# Drone-Schematic-v1.net
KiCad netlist of a schematic drawn in Altium Designer
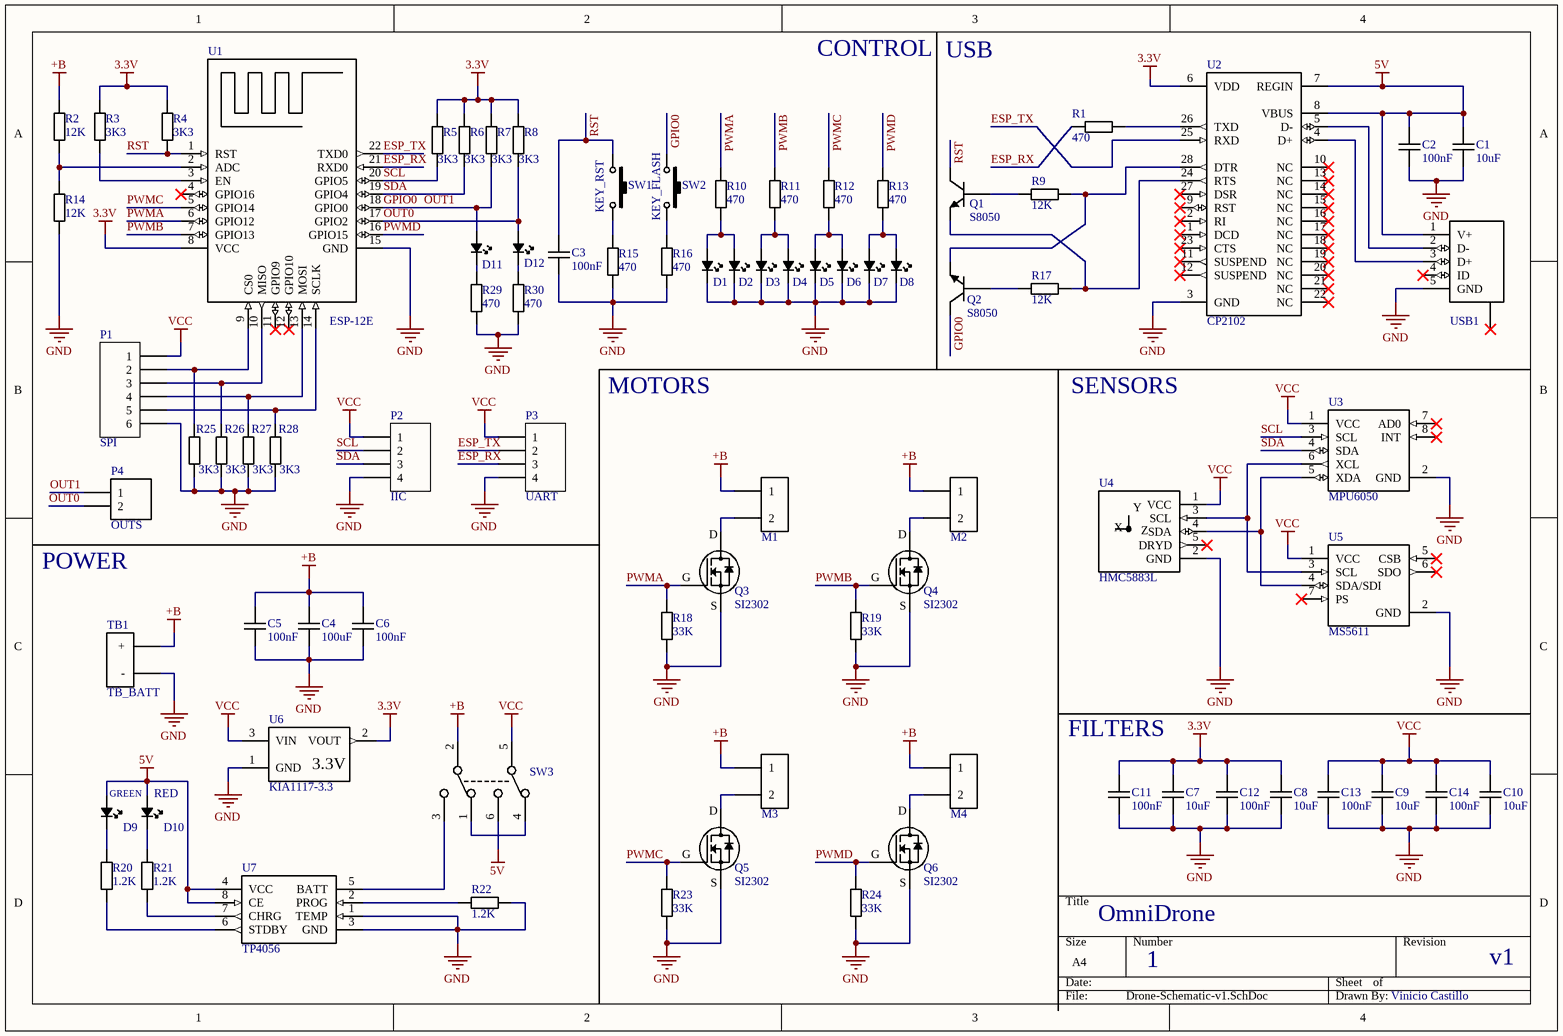
[diagram p0: Drone-Schematic-v1.SchDoc]

(export (version "E")
  (design (tool "Eeschema 10.0.6"))
  (components
    (comp (ref "C1") (value "10uF") (footprint "1206CAP") (libsource (lib "OmniLibrary") (part "Capacitor")))
    (comp (ref "C2") (value "100nF") (footprint "1206CAP") (libsource (lib "OmniLibrary") (part "Capacitor")))
    (comp (ref "C3") (value "100nF") (footprint "1206CAP") (libsource (lib "OmniLibrary") (part "Capacitor")))
    (comp (ref "C4") (value "100uF") (footprint "1206CAP") (libsource (lib "OmniLibrary") (part "Capacitor")))
    (comp (ref "C5") (value "100nF") (footprint "1206CAP") (libsource (lib "OmniLibrary") (part "Capacitor")))
    (comp (ref "C6") (value "100nF") (footprint "1206CAP") (libsource (lib "OmniLibrary") (part "Capacitor")))
    (comp (ref "C7") (value "10uF") (footprint "1206CAP") (libsource (lib "OmniLibrary") (part "Capacitor")))
    (comp (ref "C8") (value "10uF") (footprint "1206CAP") (libsource (lib "OmniLibrary") (part "Capacitor")))
    (comp (ref "C9") (value "10uF") (footprint "1206CAP") (libsource (lib "OmniLibrary") (part "Capacitor")))
    (comp (ref "C10") (value "10uF") (footprint "1206CAP") (libsource (lib "OmniLibrary") (part "Capacitor")))
    (comp (ref "C11")
      (value "100nF")
      (footprint "1206CAP")
      (libsource (lib "OmniLibrary") (part "Capacitor"))
    )
    (comp (ref "C12")
      (value "100nF")
      (footprint "1206CAP")
      (libsource (lib "OmniLibrary") (part "Capacitor"))
    )
    (comp (ref "C13")
      (value "100nF")
      (footprint "1206CAP")
      (libsource (lib "OmniLibrary") (part "Capacitor"))
    )
    (comp (ref "C14")
      (value "100nF")
      (footprint "1206CAP")
      (libsource (lib "OmniLibrary") (part "Capacitor"))
    )
    (comp (ref "D1")
      (value "LED")
      (footprint "1206DIODE")
      (description "Ligth Emitting Diode (LED)")
      (libsource (lib "OmniLibrary") (part "LED"))
    )
    (comp (ref "D2")
      (value "LED")
      (footprint "1206DIODE")
      (description "Ligth Emitting Diode (LED)")
      (libsource (lib "OmniLibrary") (part "LED"))
    )
    (comp (ref "D3")
      (value "LED")
      (footprint "1206DIODE")
      (description "Ligth Emitting Diode (LED)")
      (libsource (lib "OmniLibrary") (part "LED"))
    )
    (comp (ref "D4")
      (value "LED")
      (footprint "1206DIODE")
      (description "Ligth Emitting Diode (LED)")
      (libsource (lib "OmniLibrary") (part "LED"))
    )
    (comp (ref "D5")
      (value "LED")
      (footprint "1206DIODE")
      (description "Ligth Emitting Diode (LED)")
      (libsource (lib "OmniLibrary") (part "LED"))
    )
    (comp (ref "D6")
      (value "LED")
      (footprint "1206DIODE")
      (description "Ligth Emitting Diode (LED)")
      (libsource (lib "OmniLibrary") (part "LED"))
    )
    (comp (ref "D7")
      (value "LED")
      (footprint "1206DIODE")
      (description "Ligth Emitting Diode (LED)")
      (libsource (lib "OmniLibrary") (part "LED"))
    )
    (comp (ref "D8")
      (value "LED")
      (footprint "1206DIODE")
      (description "Ligth Emitting Diode (LED)")
      (libsource (lib "OmniLibrary") (part "LED"))
    )
    (comp (ref "D9")
      (value "LED")
      (footprint "1206DIODE")
      (description "Ligth Emitting Diode (LED)")
      (libsource (lib "OmniLibrary") (part "LED"))
    )
    (comp (ref "D10")
      (value "LED")
      (footprint "1206DIODE")
      (description "Ligth Emitting Diode (LED)")
      (libsource (lib "OmniLibrary") (part "LED"))
    )
    (comp (ref "D11")
      (value "LED")
      (footprint "1206DIODE")
      (description "Ligth Emitting Diode (LED)")
      (libsource (lib "OmniLibrary") (part "LED"))
    )
    (comp (ref "D12")
      (value "LED")
      (footprint "1206DIODE")
      (description "Ligth Emitting Diode (LED)")
      (libsource (lib "OmniLibrary") (part "LED"))
    )
    (comp (ref "M1")
      (value "TBX2X1")
      (footprint "JST 1.25mm")
      (description "Terminal Block 2 pins, 1 row")
      (libsource (lib "OmniLibrary") (part "TBX2X1"))
    )
    (comp (ref "M2")
      (value "TBX2X1")
      (footprint "JST 1.25mm")
      (description "Terminal Block 2 pins, 1 row")
      (libsource (lib "OmniLibrary") (part "TBX2X1"))
    )
    (comp (ref "M3")
      (value "TBX2X1")
      (footprint "JST 1.25mm")
      (description "Terminal Block 2 pins, 1 row")
      (libsource (lib "OmniLibrary") (part "TBX2X1"))
    )
    (comp (ref "M4")
      (value "TBX2X1")
      (footprint "JST 1.25mm")
      (description "Terminal Block 2 pins, 1 row")
      (libsource (lib "OmniLibrary") (part "TBX2X1"))
    )
    (comp (ref "P1")
      (value "SPI")
      (footprint "HDR1X6")
      (description "Header, 6-Pin")
      (fields (field (name "PUBLISHER") "Altium Limited"))
      (libsource (lib "OmniLibrary") (part "Header 6"))
    )
    (comp (ref "P2")
      (value "IIC")
      (footprint "HDR1X4")
      (description "Header, 4-Pin")
      (fields (field (name "PUBLISHER") "Altium Limited"))
      (libsource (lib "OmniLibrary") (part "Header 4"))
    )
    (comp (ref "P3")
      (value "UART")
      (footprint "HDR1X4")
      (description "Header, 4-Pin")
      (fields (field (name "PUBLISHER") "Altium Limited"))
      (libsource (lib "OmniLibrary") (part "Header 4"))
    )
    (comp (ref "P4")
      (value "OUTS")
      (footprint "HDR1X2")
      (description "Header, 2-Pin")
      (fields (field (name "PUBLISHER") "Altium Limited"))
      (libsource (lib "OmniLibrary") (part "Header 2"))
    )
    (comp (ref "Q1")
      (value "S8050")
      (footprint "SOT-23(SOT-23-3)")
      (description "Transistor NPN 500mA 25V SOT-23(SOT-23-3) RoHS")
      (libsource (lib "OmniLibrary") (part "S8050"))
    )
    (comp (ref "Q2")
      (value "S8050")
      (footprint "SOT-23(SOT-23-3)")
      (description "Transistor NPN 500mA 25V SOT-23(SOT-23-3) RoHS")
      (libsource (lib "OmniLibrary") (part "S8050"))
    )
    (comp (ref "Q3")
      (value "SI2302")
      (footprint "SOT-23(SOT-23-3)")
      (description "MOSFET N Trench 20V 2.1A 1.2V @ 50uA 72 mO @ 3.6A,4.5V SOT-23(SOT-23-3) RoHS")
      (libsource (lib "OmniLibrary") (part "SI2302"))
    )
    (comp (ref "Q4")
      (value "SI2302")
      (footprint "SOT-23(SOT-23-3)")
      (description "MOSFET N Trench 20V 2.1A 1.2V @ 50uA 72 mO @ 3.6A,4.5V SOT-23(SOT-23-3) RoHS")
      (libsource (lib "OmniLibrary") (part "SI2302"))
    )
    (comp (ref "Q5")
      (value "SI2302")
      (footprint "SOT-23(SOT-23-3)")
      (description "MOSFET N Trench 20V 2.1A 1.2V @ 50uA 72 mO @ 3.6A,4.5V SOT-23(SOT-23-3) RoHS")
      (libsource (lib "OmniLibrary") (part "SI2302"))
    )
    (comp (ref "Q6")
      (value "SI2302")
      (footprint "SOT-23(SOT-23-3)")
      (description "MOSFET N Trench 20V 2.1A 1.2V @ 50uA 72 mO @ 3.6A,4.5V SOT-23(SOT-23-3) RoHS")
      (libsource (lib "OmniLibrary") (part "SI2302"))
    )
    (comp (ref "R1")
      (value "470")
      (footprint "1206RES")
      (description "Passive component")
      (libsource (lib "") (part "Resistor_2"))
    )
    (comp (ref "R2")
      (value "12K")
      (footprint "1206RES")
      (description "Passive component")
      (libsource (lib "OmniLibrary") (part "Resistor"))
    )
    (comp (ref "R3")
      (value "3K3")
      (footprint "1206RES")
      (description "Passive component")
      (libsource (lib "") (part "Resistor_1"))
    )
    (comp (ref "R4")
      (value "3K3")
      (footprint "1206RES")
      (description "Passive component")
      (libsource (lib "") (part "Resistor_1"))
    )
    (comp (ref "R5")
      (value "3K3")
      (footprint "1206RES")
      (description "Passive component")
      (libsource (lib "") (part "Resistor_1"))
    )
    (comp (ref "R6")
      (value "3K3")
      (footprint "1206RES")
      (description "Passive component")
      (libsource (lib "") (part "Resistor_1"))
    )
    (comp (ref "R7")
      (value "3K3")
      (footprint "1206RES")
      (description "Passive component")
      (libsource (lib "") (part "Resistor_1"))
    )
    (comp (ref "R8")
      (value "3K3")
      (footprint "1206RES")
      (description "Passive component")
      (libsource (lib "") (part "Resistor_1"))
    )
    (comp (ref "R9")
      (value "12K")
      (footprint "1206RES")
      (description "Passive component")
      (libsource (lib "") (part "Resistor_2"))
    )
    (comp (ref "R10")
      (value "470")
      (footprint "1206RES")
      (description "Passive component")
      (libsource (lib "") (part "Resistor_1"))
    )
    (comp (ref "R11")
      (value "470")
      (footprint "1206RES")
      (description "Passive component")
      (libsource (lib "") (part "Resistor_1"))
    )
    (comp (ref "R12")
      (value "470")
      (footprint "1206RES")
      (description "Passive component")
      (libsource (lib "") (part "Resistor_1"))
    )
    (comp (ref "R13")
      (value "470")
      (footprint "1206RES")
      (description "Passive component")
      (libsource (lib "") (part "Resistor_1"))
    )
    (comp (ref "R14")
      (value "12K")
      (footprint "1206RES")
      (description "Passive component")
      (libsource (lib "OmniLibrary") (part "Resistor"))
    )
    (comp (ref "R15")
      (value "470")
      (footprint "1206RES")
      (description "Passive component")
      (libsource (lib "") (part "Resistor_1"))
    )
    (comp (ref "R16")
      (value "470")
      (footprint "1206RES")
      (description "Passive component")
      (libsource (lib "") (part "Resistor_1"))
    )
    (comp (ref "R17")
      (value "12K")
      (footprint "1206RES")
      (description "Passive component")
      (libsource (lib "") (part "Resistor_2"))
    )
    (comp (ref "R18")
      (value "33K")
      (footprint "1206RES")
      (description "Passive component")
      (libsource (lib "OmniLibrary") (part "Resistor"))
    )
    (comp (ref "R19")
      (value "33K")
      (footprint "1206RES")
      (description "Passive component")
      (libsource (lib "OmniLibrary") (part "Resistor"))
    )
    (comp (ref "R20")
      (value "1.2K")
      (footprint "1206RES")
      (description "Passive component")
      (libsource (lib "OmniLibrary") (part "Resistor"))
    )
    (comp (ref "R21")
      (value "1.2K")
      (footprint "1206RES")
      (description "Passive component")
      (libsource (lib "OmniLibrary") (part "Resistor"))
    )
    (comp (ref "R22")
      (value "1.2K")
      (footprint "1206RES")
      (description "Passive component")
      (libsource (lib "") (part "Resistor_2"))
    )
    (comp (ref "R23")
      (value "33K")
      (footprint "1206RES")
      (description "Passive component")
      (libsource (lib "OmniLibrary") (part "Resistor"))
    )
    (comp (ref "R24")
      (value "33K")
      (footprint "1206RES")
      (description "Passive component")
      (libsource (lib "OmniLibrary") (part "Resistor"))
    )
    (comp (ref "R25")
      (value "3K3")
      (footprint "1206RES")
      (description "Passive component")
      (libsource (lib "") (part "Resistor_1"))
    )
    (comp (ref "R26")
      (value "3K3")
      (footprint "1206RES")
      (description "Passive component")
      (libsource (lib "") (part "Resistor_1"))
    )
    (comp (ref "R27")
      (value "3K3")
      (footprint "1206RES")
      (description "Passive component")
      (libsource (lib "") (part "Resistor_1"))
    )
    (comp (ref "R28")
      (value "3K3")
      (footprint "1206RES")
      (description "Passive component")
      (libsource (lib "") (part "Resistor_1"))
    )
    (comp (ref "R29")
      (value "470")
      (footprint "1206RES")
      (description "Passive component")
      (libsource (lib "OmniLibrary") (part "Resistor"))
    )
    (comp (ref "R30")
      (value "470")
      (footprint "1206RES")
      (description "Passive component")
      (libsource (lib "OmniLibrary") (part "Resistor"))
    )
    (comp (ref "SW1")
      (value "PUSH BUTTON")
      (footprint "Push Button")
      (description "Normally Open (NO) button")
      (libsource (lib "OmniLibrary") (part "PUSH BUTTON"))
    )
    (comp (ref "SW2")
      (value "PUSH BUTTON")
      (footprint "Push Button")
      (description "Normally Open (NO) button")
      (libsource (lib "OmniLibrary") (part "PUSH BUTTON"))
    )
    (comp (ref "SW3")
      (value "SW DPDT")
      (footprint "DPDT SW")
      (description "DPDT Switch")
      (libsource (lib "OmniLibrary") (part "SW DPDT"))
    )
    (comp (ref "TB1")
      (value "TB_BATT")
      (footprint "2P PH2.0mm Pitch")
      (description "Battery terminal block")
      (libsource (lib "OmniLibrary") (part "TB_BATT"))
    )
    (comp (ref "U1")
      (value "ESP-12E")
      (footprint "ESP-12E")
      (description "ESP8266 MCU based WIFI PCB Module")
      (libsource (lib "OmniLibrary") (part "ESP-12E"))
    )
    (comp (ref "U2")
      (value "CP2102")
      (footprint "CP2102")
      (description "USB to UART interface IC 3.3v")
      (libsource (lib "OmniLibrary") (part "CP2102"))
    )
    (comp (ref "U3")
      (value "MPU6050")
      (footprint "MPU6050 - PCB MODULE")
      (description "PCB Module, 3 Axis Analog Gyro Sensors+ 3 Axis Accelerometer, IIC")
      (libsource (lib "OmniLibrary") (part "MPU6050"))
    )
    (comp (ref "U4")
      (value "HMC5883L")
      (footprint "HMC5883L - PCB MODULE")
      (description "PCB Module, Triple Axis Compass Magnetometer Sensor Module, IIC Conn")
      (libsource (lib "OmniLibrary") (part "HMC5883L"))
    )
    (comp (ref "U5")
      (value "MS5611")
      (footprint "MS5611 - PCB MODULE")
      (description "PCB Module, Atmospheric Pressure Sensor Module Meter Altimeter Sensor Module, IIC")
      (libsource (lib "OmniLibrary") (part "MS5611"))
    )
    (comp (ref "U6")
      (value "KIA1117-3.3")
      (footprint "KIA1117-3.3")
      (description "LOD and Fixed positive voltage regulator 3.3V 1A")
      (libsource (lib "OmniLibrary") (part "KIA1117-3.3"))
    )
    (comp (ref "U7")
      (value "TP4056")
      (footprint "TP4056")
      (description "1A Standalone Linear Li-lon Battery Charger with Thermal  Regulation in SOP-8")
      (libsource (lib "OmniLibrary") (part "TP4056"))
    )
    (comp (ref "USB1")
      (value "USB Connector")
      (footprint "USB micro Female")
      (libsource (lib "OmniLibrary") (part "USB"))
    )
  )
  (nets
    (net (code "1") (name "+B") (class "Default")
      (node (ref "C4") (pin "2") (pinfunction "2_2") (pintype "passive"))
      (node (ref "C5") (pin "2") (pinfunction "2_2") (pintype "passive"))
      (node (ref "C6") (pin "2") (pinfunction "2_2") (pintype "passive"))
      (node (ref "M1") (pin "1") (pinfunction "1_1") (pintype "passive"))
      (node (ref "M2") (pin "1") (pinfunction "1_1") (pintype "passive"))
      (node (ref "M3") (pin "1") (pinfunction "1_1") (pintype "passive"))
      (node (ref "M4") (pin "1") (pinfunction "1_1") (pintype "passive"))
      (node (ref "R2") (pin "1") (pinfunction "1_1") (pintype "passive"))
      (node (ref "SW3") (pin "2") (pinfunction "2_2") (pintype "passive"))
      (node (ref "TB1") (pin "1") (pinfunction "+_1") (pintype "power_in"))
    )
    (net (code "2") (name "/ESP_RX") (class "Default")
      (node (ref "P3") (pin "3") (pinfunction "3_3") (pintype "passive"))
      (node (ref "R1") (pin "2") (pinfunction "2_2") (pintype "passive"))
      (node (ref "U1") (pin "21") (pinfunction "RXD0_21") (pintype "input"))
    )
    (net (code "3") (name "/ESP_TX") (class "Default")
      (node (ref "P3") (pin "2") (pinfunction "2_2") (pintype "passive"))
      (node (ref "U1") (pin "22") (pinfunction "TXD0_22") (pintype "output"))
      (node (ref "U2") (pin "25") (pinfunction "RXD_25") (pintype "input"))
    )
    (net (code "4") (name "/GPIO0") (class "Default")
      (node (ref "D11") (pin "1") (pinfunction "1_1") (pintype "passive"))
      (node (ref "P4") (pin "1") (pinfunction "1_1") (pintype "passive"))
      (node (ref "Q2") (pin "3") (pinfunction "C_3") (pintype "passive"))
      (node (ref "R7") (pin "1") (pinfunction "1_1") (pintype "passive"))
      (node (ref "SW2") (pin "1") (pinfunction "1_1") (pintype "passive"))
      (node (ref "U1") (pin "18") (pinfunction "GPIO0_18") (pintype "bidirectional"))
    )
    (net (code "5") (name "/OUT0") (class "Default")
      (node (ref "D12") (pin "1") (pinfunction "1_1") (pintype "passive"))
      (node (ref "P4") (pin "2") (pinfunction "2_2") (pintype "passive"))
      (node (ref "R8") (pin "1") (pinfunction "1_1") (pintype "passive"))
      (node (ref "U1") (pin "17") (pinfunction "GPIO2_17") (pintype "bidirectional"))
    )
    (net (code "6") (name "/PWMA") (class "Default")
      (node (ref "Q3") (pin "1") (pinfunction "G_1") (pintype "passive"))
      (node (ref "R10") (pin "2") (pinfunction "2_2") (pintype "passive"))
      (node (ref "R18") (pin "1") (pinfunction "1_1") (pintype "passive"))
      (node (ref "U1") (pin "6") (pinfunction "GPIO12_6") (pintype "bidirectional"))
    )
    (net (code "7") (name "/PWMB") (class "Default")
      (node (ref "Q4") (pin "1") (pinfunction "G_1") (pintype "passive"))
      (node (ref "R11") (pin "2") (pinfunction "2_2") (pintype "passive"))
      (node (ref "R19") (pin "1") (pinfunction "1_1") (pintype "passive"))
      (node (ref "U1") (pin "7") (pinfunction "GPIO13_7") (pintype "bidirectional"))
    )
    (net (code "8") (name "/PWMC") (class "Default")
      (node (ref "Q5") (pin "1") (pinfunction "G_1") (pintype "passive"))
      (node (ref "R12") (pin "2") (pinfunction "2_2") (pintype "passive"))
      (node (ref "R23") (pin "1") (pinfunction "1_1") (pintype "passive"))
      (node (ref "U1") (pin "5") (pinfunction "GPIO14_5") (pintype "bidirectional"))
    )
    (net (code "9") (name "/PWMD") (class "Default")
      (node (ref "Q6") (pin "1") (pinfunction "G_1") (pintype "passive"))
      (node (ref "R13") (pin "2") (pinfunction "2_2") (pintype "passive"))
      (node (ref "R24") (pin "1") (pinfunction "1_1") (pintype "passive"))
      (node (ref "U1") (pin "16") (pinfunction "GPIO15_16") (pintype "bidirectional"))
    )
    (net (code "10") (name "/RST") (class "Default")
      (node (ref "C3") (pin "2") (pinfunction "2_2") (pintype "passive"))
      (node (ref "Q1") (pin "3") (pinfunction "C_3") (pintype "passive"))
      (node (ref "R4") (pin "1") (pinfunction "1_1") (pintype "passive"))
      (node (ref "SW1") (pin "1") (pinfunction "1_1") (pintype "passive"))
      (node (ref "U1") (pin "1") (pinfunction "RST_1") (pintype "input"))
    )
    (net (code "11") (name "/SCL") (class "Default")
      (node (ref "P2") (pin "2") (pinfunction "2_2") (pintype "passive"))
      (node (ref "R5") (pin "1") (pinfunction "1_1") (pintype "passive"))
      (node (ref "U1") (pin "20") (pinfunction "GPIO5_20") (pintype "bidirectional"))
      (node (ref "U3") (pin "3") (pinfunction "SCL_3") (pintype "input"))
    )
    (net (code "12") (name "/SDA") (class "Default")
      (node (ref "P2") (pin "3") (pinfunction "3_3") (pintype "passive"))
      (node (ref "R6") (pin "1") (pinfunction "1_1") (pintype "passive"))
      (node (ref "U1") (pin "19") (pinfunction "GPIO4_19") (pintype "bidirectional"))
      (node (ref "U3") (pin "4") (pinfunction "SDA_4") (pintype "bidirectional"))
    )
    (net (code "13") (name "3.3V") (class "Default")
      (node (ref "C11") (pin "2") (pinfunction "2_2") (pintype "passive"))
      (node (ref "C12") (pin "2") (pinfunction "2_2") (pintype "passive"))
      (node (ref "C7") (pin "2") (pinfunction "2_2") (pintype "passive"))
      (node (ref "C8") (pin "2") (pinfunction "2_2") (pintype "passive"))
      (node (ref "R3") (pin "2") (pinfunction "2_2") (pintype "passive"))
      (node (ref "R4") (pin "2") (pinfunction "2_2") (pintype "passive"))
      (node (ref "R5") (pin "2") (pinfunction "2_2") (pintype "passive"))
      (node (ref "R6") (pin "2") (pinfunction "2_2") (pintype "passive"))
      (node (ref "R7") (pin "2") (pinfunction "2_2") (pintype "passive"))
      (node (ref "R8") (pin "2") (pinfunction "2_2") (pintype "passive"))
      (node (ref "U1") (pin "8") (pinfunction "VCC_8") (pintype "power_in"))
      (node (ref "U2") (pin "6") (pinfunction "VDD_6") (pintype "power_in"))
      (node (ref "U6") (pin "2") (pinfunction "VOUT_2") (pintype "output"))
    )
    (net (code "14") (name "5V") (class "Default")
      (node (ref "C1") (pin "2") (pinfunction "2_2") (pintype "passive"))
      (node (ref "C2") (pin "2") (pinfunction "2_2") (pintype "passive"))
      (node (ref "D10") (pin "1") (pinfunction "1_1") (pintype "passive"))
      (node (ref "D9") (pin "1") (pinfunction "1_1") (pintype "passive"))
      (node (ref "SW3") (pin "6") (pinfunction "6_6") (pintype "passive"))
      (node (ref "U2") (pin "7") (pinfunction "REGIN_7") (pintype "power_in"))
      (node (ref "U2") (pin "8") (pinfunction "VBUS_8") (pintype "power_in"))
      (node (ref "U7") (pin "4") (pinfunction "VCC_4") (pintype "power_in"))
      (node (ref "U7") (pin "8") (pinfunction "CE_8") (pintype "input"))
      (node (ref "USB1") (pin "1") (pinfunction "V+_1") (pintype "power_in"))
    )
    (net (code "15") (name "GND") (class "Default")
      (node (ref "C1") (pin "1") (pinfunction "1_1") (pintype "passive"))
      (node (ref "C10") (pin "1") (pinfunction "1_1") (pintype "passive"))
      (node (ref "C11") (pin "1") (pinfunction "1_1") (pintype "passive"))
      (node (ref "C12") (pin "1") (pinfunction "1_1") (pintype "passive"))
      (node (ref "C13") (pin "1") (pinfunction "1_1") (pintype "passive"))
      (node (ref "C14") (pin "1") (pinfunction "1_1") (pintype "passive"))
      (node (ref "C2") (pin "1") (pinfunction "1_1") (pintype "passive"))
      (node (ref "C3") (pin "1") (pinfunction "1_1") (pintype "passive"))
      (node (ref "C4") (pin "1") (pinfunction "1_1") (pintype "passive"))
      (node (ref "C5") (pin "1") (pinfunction "1_1") (pintype "passive"))
      (node (ref "C6") (pin "1") (pinfunction "1_1") (pintype "passive"))
      (node (ref "C7") (pin "1") (pinfunction "1_1") (pintype "passive"))
      (node (ref "C8") (pin "1") (pinfunction "1_1") (pintype "passive"))
      (node (ref "C9") (pin "1") (pinfunction "1_1") (pintype "passive"))
      (node (ref "D1") (pin "2") (pinfunction "2_2") (pintype "passive"))
      (node (ref "D2") (pin "2") (pinfunction "2_2") (pintype "passive"))
      (node (ref "D3") (pin "2") (pinfunction "2_2") (pintype "passive"))
      (node (ref "D4") (pin "2") (pinfunction "2_2") (pintype "passive"))
      (node (ref "D5") (pin "2") (pinfunction "2_2") (pintype "passive"))
      (node (ref "D6") (pin "2") (pinfunction "2_2") (pintype "passive"))
      (node (ref "D7") (pin "2") (pinfunction "2_2") (pintype "passive"))
      (node (ref "D8") (pin "2") (pinfunction "2_2") (pintype "passive"))
      (node (ref "P1") (pin "6") (pinfunction "6_6") (pintype "passive"))
      (node (ref "P2") (pin "4") (pinfunction "4_4") (pintype "passive"))
      (node (ref "P3") (pin "4") (pinfunction "4_4") (pintype "passive"))
      (node (ref "Q3") (pin "2") (pinfunction "S_2") (pintype "passive"))
      (node (ref "Q4") (pin "2") (pinfunction "S_2") (pintype "passive"))
      (node (ref "Q5") (pin "2") (pinfunction "S_2") (pintype "passive"))
      (node (ref "Q6") (pin "2") (pinfunction "S_2") (pintype "passive"))
      (node (ref "R14") (pin "2") (pinfunction "2_2") (pintype "passive"))
      (node (ref "R15") (pin "1") (pinfunction "1_1") (pintype "passive"))
      (node (ref "R16") (pin "1") (pinfunction "1_1") (pintype "passive"))
      (node (ref "R18") (pin "2") (pinfunction "2_2") (pintype "passive"))
      (node (ref "R19") (pin "2") (pinfunction "2_2") (pintype "passive"))
      (node (ref "R22") (pin "1") (pinfunction "1_1") (pintype "passive"))
      (node (ref "R23") (pin "2") (pinfunction "2_2") (pintype "passive"))
      (node (ref "R24") (pin "2") (pinfunction "2_2") (pintype "passive"))
      (node (ref "R25") (pin "1") (pinfunction "1_1") (pintype "passive"))
      (node (ref "R26") (pin "1") (pinfunction "1_1") (pintype "passive"))
      (node (ref "R27") (pin "1") (pinfunction "1_1") (pintype "passive"))
      (node (ref "R28") (pin "1") (pinfunction "1_1") (pintype "passive"))
      (node (ref "R29") (pin "2") (pinfunction "2_2") (pintype "passive"))
      (node (ref "R30") (pin "2") (pinfunction "2_2") (pintype "passive"))
      (node (ref "TB1") (pin "2") (pinfunction "-_2") (pintype "power_in"))
      (node (ref "U1") (pin "15") (pinfunction "GND_15") (pintype "power_in"))
      (node (ref "U2") (pin "3") (pinfunction "GND_3") (pintype "power_in"))
      (node (ref "U3") (pin "2") (pinfunction "GND_2") (pintype "power_in"))
      (node (ref "U4") (pin "2") (pinfunction "GND_2") (pintype "power_in"))
      (node (ref "U5") (pin "2") (pinfunction "GND_2") (pintype "power_in"))
      (node (ref "U6") (pin "1") (pinfunction "GND_1") (pintype "power_in"))
      (node (ref "U7") (pin "1") (pinfunction "TEMP_1") (pintype "input"))
      (node (ref "U7") (pin "3") (pinfunction "GND_3") (pintype "power_in"))
      (node (ref "USB1") (pin "5") (pinfunction "GND_5") (pintype "power_in"))
    )
    (net (code "16") (name "Net-(D1-Pad1)") (class "Default")
      (node (ref "D1") (pin "1") (pinfunction "1_1") (pintype "passive"))
      (node (ref "D2") (pin "1") (pinfunction "1_1") (pintype "passive"))
      (node (ref "R10") (pin "1") (pinfunction "1_1") (pintype "passive"))
    )
    (net (code "17") (name "Net-(D3-Pad1)") (class "Default")
      (node (ref "D3") (pin "1") (pinfunction "1_1") (pintype "passive"))
      (node (ref "D4") (pin "1") (pinfunction "1_1") (pintype "passive"))
      (node (ref "R11") (pin "1") (pinfunction "1_1") (pintype "passive"))
    )
    (net (code "18") (name "Net-(D5-Pad1)") (class "Default")
      (node (ref "D5") (pin "1") (pinfunction "1_1") (pintype "passive"))
      (node (ref "D6") (pin "1") (pinfunction "1_1") (pintype "passive"))
      (node (ref "R12") (pin "1") (pinfunction "1_1") (pintype "passive"))
    )
    (net (code "19") (name "Net-(D7-Pad1)") (class "Default")
      (node (ref "D7") (pin "1") (pinfunction "1_1") (pintype "passive"))
      (node (ref "D8") (pin "1") (pinfunction "1_1") (pintype "passive"))
      (node (ref "R13") (pin "1") (pinfunction "1_1") (pintype "passive"))
    )
    (net (code "20") (name "Net-(D9-Pad2)") (class "Default")
      (node (ref "D9") (pin "2") (pinfunction "2_2") (pintype "passive"))
      (node (ref "R20") (pin "1") (pinfunction "1_1") (pintype "passive"))
    )
    (net (code "21") (name "Net-(D10-Pad2)") (class "Default")
      (node (ref "D10") (pin "2") (pinfunction "2_2") (pintype "passive"))
      (node (ref "R21") (pin "1") (pinfunction "1_1") (pintype "passive"))
    )
    (net (code "22") (name "Net-(D11-Pad2)") (class "Default")
      (node (ref "D11") (pin "2") (pinfunction "2_2") (pintype "passive"))
      (node (ref "R29") (pin "1") (pinfunction "1_1") (pintype "passive"))
    )
    (net (code "23") (name "Net-(D12-Pad2)") (class "Default")
      (node (ref "D12") (pin "2") (pinfunction "2_2") (pintype "passive"))
      (node (ref "R30") (pin "1") (pinfunction "1_1") (pintype "passive"))
    )
    (net (code "24") (name "Net-(Q1-B)") (class "Default")
      (node (ref "Q1") (pin "1") (pinfunction "B_1") (pintype "passive"))
      (node (ref "R9") (pin "2") (pinfunction "2_2") (pintype "passive"))
    )
    (net (code "25") (name "Net-(Q1-E)") (class "Default")
      (node (ref "Q1") (pin "2") (pinfunction "E_2") (pintype "passive"))
      (node (ref "R17") (pin "1") (pinfunction "1_1") (pintype "passive"))
      (node (ref "U2") (pin "24") (pinfunction "RTS_24") (pintype "output"))
    )
    (net (code "26") (name "Net-(Q2-B)") (class "Default")
      (node (ref "Q2") (pin "1") (pinfunction "B_1") (pintype "passive"))
      (node (ref "R17") (pin "2") (pinfunction "2_2") (pintype "passive"))
    )
    (net (code "27") (name "Net-(Q2-E)") (class "Default")
      (node (ref "Q2") (pin "2") (pinfunction "E_2") (pintype "passive"))
      (node (ref "R9") (pin "1") (pinfunction "1_1") (pintype "passive"))
      (node (ref "U2") (pin "28") (pinfunction "DTR_28") (pintype "output"))
    )
    (net (code "28") (name "Net-(Q3-D)") (class "Default")
      (node (ref "M1") (pin "2") (pinfunction "2_2") (pintype "passive"))
      (node (ref "Q3") (pin "3") (pinfunction "D_3") (pintype "passive"))
    )
    (net (code "29") (name "Net-(Q4-D)") (class "Default")
      (node (ref "M2") (pin "2") (pinfunction "2_2") (pintype "passive"))
      (node (ref "Q4") (pin "3") (pinfunction "D_3") (pintype "passive"))
    )
    (net (code "30") (name "Net-(Q5-D)") (class "Default")
      (node (ref "M3") (pin "2") (pinfunction "2_2") (pintype "passive"))
      (node (ref "Q5") (pin "3") (pinfunction "D_3") (pintype "passive"))
    )
    (net (code "31") (name "Net-(Q6-D)") (class "Default")
      (node (ref "M4") (pin "2") (pinfunction "2_2") (pintype "passive"))
      (node (ref "Q6") (pin "3") (pinfunction "D_3") (pintype "passive"))
    )
    (net (code "32") (name "Net-(R15-Pad2)") (class "Default")
      (node (ref "R15") (pin "2") (pinfunction "2_2") (pintype "passive"))
      (node (ref "SW1") (pin "2") (pinfunction "2_2") (pintype "passive"))
    )
    (net (code "33") (name "Net-(R16-Pad2)") (class "Default")
      (node (ref "R16") (pin "2") (pinfunction "2_2") (pintype "passive"))
      (node (ref "SW2") (pin "2") (pinfunction "2_2") (pintype "passive"))
    )
    (net (code "34") (name "Net-(SW3-Pad1)") (class "Default")
      (node (ref "SW3") (pin "1") (pinfunction "1_1") (pintype "passive"))
      (node (ref "SW3") (pin "4") (pinfunction "4_4") (pintype "passive"))
    )
    (net (code "35") (name "Net-(U1-ADC)") (class "Default")
      (node (ref "R14") (pin "1") (pinfunction "1_1") (pintype "passive"))
      (node (ref "R2") (pin "2") (pinfunction "2_2") (pintype "passive"))
      (node (ref "U1") (pin "2") (pinfunction "ADC_2") (pintype "input"))
    )
    (net (code "36") (name "Net-(U1-CS0)") (class "Default")
      (node (ref "P1") (pin "2") (pinfunction "2_2") (pintype "passive"))
      (node (ref "R25") (pin "2") (pinfunction "2_2") (pintype "passive"))
      (node (ref "U1") (pin "9") (pinfunction "CS0_9") (pintype "input"))
    )
    (net (code "37") (name "Net-(U1-EN)") (class "Default")
      (node (ref "R3") (pin "1") (pinfunction "1_1") (pintype "passive"))
      (node (ref "U1") (pin "3") (pinfunction "EN_3") (pintype "input"))
    )
    (net (code "38") (name "Net-(U1-MISO)") (class "Default")
      (node (ref "P1") (pin "3") (pinfunction "3_3") (pintype "passive"))
      (node (ref "R26") (pin "2") (pinfunction "2_2") (pintype "passive"))
      (node (ref "U1") (pin "10") (pinfunction "MISO_10") (pintype "output"))
    )
    (net (code "39") (name "Net-(U1-MOSI)") (class "Default")
      (node (ref "P1") (pin "4") (pinfunction "4_4") (pintype "passive"))
      (node (ref "R27") (pin "2") (pinfunction "2_2") (pintype "passive"))
      (node (ref "U1") (pin "13") (pinfunction "MOSI_13") (pintype "input"))
    )
    (net (code "40") (name "Net-(U1-SCLK)") (class "Default")
      (node (ref "P1") (pin "5") (pinfunction "5_5") (pintype "passive"))
      (node (ref "R28") (pin "2") (pinfunction "2_2") (pintype "passive"))
      (node (ref "U1") (pin "14") (pinfunction "SCLK_14") (pintype "input"))
    )
    (net (code "41") (name "Net-(U2-D+)") (class "Default")
      (node (ref "U2") (pin "4") (pinfunction "D+_4") (pintype "bidirectional"))
      (node (ref "USB1") (pin "3") (pinfunction "D+_3") (pintype "bidirectional"))
    )
    (net (code "42") (name "Net-(U2-D-)") (class "Default")
      (node (ref "U2") (pin "5") (pinfunction "D-_5") (pintype "bidirectional"))
      (node (ref "USB1") (pin "2") (pinfunction "D-_2") (pintype "bidirectional"))
    )
    (net (code "43") (name "Net-(U2-TXD)") (class "Default")
      (node (ref "R1") (pin "1") (pinfunction "1_1") (pintype "passive"))
      (node (ref "U2") (pin "26") (pinfunction "TXD_26") (pintype "output"))
    )
    (net (code "44") (name "Net-(U3-XCL)") (class "Default")
      (node (ref "U3") (pin "6") (pinfunction "XCL_6") (pintype "output"))
      (node (ref "U4") (pin "3") (pinfunction "SCL_3") (pintype "input"))
      (node (ref "U5") (pin "3") (pinfunction "SCL_3") (pintype "input"))
    )
    (net (code "45") (name "Net-(U3-XDA)") (class "Default")
      (node (ref "U3") (pin "5") (pinfunction "XDA_5") (pintype "bidirectional"))
      (node (ref "U4") (pin "4") (pinfunction "SDA_4") (pintype "bidirectional"))
      (node (ref "U5") (pin "4") (pinfunction "SDA/SDI_4") (pintype "bidirectional"))
    )
    (net (code "46") (name "Net-(U7-BATT)") (class "Default")
      (node (ref "SW3") (pin "3") (pinfunction "3_3") (pintype "passive"))
      (node (ref "U7") (pin "5") (pinfunction "BATT_5") (pintype "power_in"))
    )
    (net (code "47") (name "Net-(U7-CHRG)") (class "Default")
      (node (ref "R21") (pin "2") (pinfunction "2_2") (pintype "passive"))
      (node (ref "U7") (pin "7") (pinfunction "CHRG_7") (pintype "output"))
    )
    (net (code "48") (name "Net-(U7-PROG)") (class "Default")
      (node (ref "R22") (pin "2") (pinfunction "2_2") (pintype "passive"))
      (node (ref "U7") (pin "2") (pinfunction "PROG_2") (pintype "input"))
    )
    (net (code "49") (name "Net-(U7-STDBY)") (class "Default")
      (node (ref "R20") (pin "2") (pinfunction "2_2") (pintype "passive"))
      (node (ref "U7") (pin "6") (pinfunction "STDBY_6") (pintype "output"))
    )
    (net (code "50") (name "VCC") (class "Default")
      (node (ref "C10") (pin "2") (pinfunction "2_2") (pintype "passive"))
      (node (ref "C13") (pin "2") (pinfunction "2_2") (pintype "passive"))
      (node (ref "C14") (pin "2") (pinfunction "2_2") (pintype "passive"))
      (node (ref "C9") (pin "2") (pinfunction "2_2") (pintype "passive"))
      (node (ref "P1") (pin "1") (pinfunction "1_1") (pintype "passive"))
      (node (ref "P2") (pin "1") (pinfunction "1_1") (pintype "passive"))
      (node (ref "P3") (pin "1") (pinfunction "1_1") (pintype "passive"))
      (node (ref "SW3") (pin "5") (pinfunction "5_5") (pintype "passive"))
      (node (ref "U3") (pin "1") (pinfunction "VCC_1") (pintype "power_in"))
      (node (ref "U4") (pin "1") (pinfunction "VCC_1") (pintype "power_in"))
      (node (ref "U5") (pin "1") (pinfunction "VCC_1") (pintype "power_in"))
      (node (ref "U6") (pin "3") (pinfunction "VIN_3") (pintype "power_in"))
    )
    (net (code "51") (name "unconnected-(SW1-Pad0)") (class "Default")
      (node (ref "SW1") (pin "0") (pinfunction "0_0") (pintype "passive"))
    )
    (net (code "52") (name "unconnected-(SW2-Pad0)") (class "Default")
      (node (ref "SW2") (pin "0") (pinfunction "0_0") (pintype "passive"))
    )
    (net (code "53") (name "unconnected-(U1-GPIO9-Pad11)") (class "Default")
      (node (ref "U1") (pin "11") (pinfunction "GPIO9_11") (pintype "bidirectional+no_connect"))
    )
    (net (code "54") (name "unconnected-(U1-GPIO10-Pad12)") (class "Default")
      (node (ref "U1") (pin "12") (pinfunction "GPIO10_12") (pintype "bidirectional+no_connect"))
    )
    (net (code "55") (name "unconnected-(U1-GPIO16-Pad4)") (class "Default")
      (node (ref "U1") (pin "4") (pinfunction "GPIO16_4") (pintype "bidirectional+no_connect"))
    )
    (net (code "56") (name "unconnected-(U2-CTS-Pad23)") (class "Default")
      (node (ref "U2") (pin "23") (pinfunction "CTS_23") (pintype "input+no_connect"))
    )
    (net (code "57") (name "unconnected-(U2-DCD-Pad1)") (class "Default")
      (node (ref "U2") (pin "1") (pinfunction "DCD_1") (pintype "input+no_connect"))
    )
    (net (code "58") (name "unconnected-(U2-DSR-Pad27)") (class "Default")
      (node (ref "U2") (pin "27") (pinfunction "DSR_27") (pintype "input+no_connect"))
    )
    (net (code "59") (name "unconnected-(U2-NC-Pad10)") (class "Default")
      (node (ref "U2") (pin "10") (pinfunction "NC_10") (pintype "passive+no_connect"))
    )
    (net (code "60") (name "unconnected-(U2-NC-Pad13)") (class "Default")
      (node (ref "U2") (pin "13") (pinfunction "NC_13") (pintype "passive+no_connect"))
    )
    (net (code "61") (name "unconnected-(U2-NC-Pad14)") (class "Default")
      (node (ref "U2") (pin "14") (pinfunction "NC_14") (pintype "passive+no_connect"))
    )
    (net (code "62") (name "unconnected-(U2-NC-Pad15)") (class "Default")
      (node (ref "U2") (pin "15") (pinfunction "NC_15") (pintype "passive+no_connect"))
    )
    (net (code "63") (name "unconnected-(U2-NC-Pad16)") (class "Default")
      (node (ref "U2") (pin "16") (pinfunction "NC_16") (pintype "passive+no_connect"))
    )
    (net (code "64") (name "unconnected-(U2-NC-Pad17)") (class "Default")
      (node (ref "U2") (pin "17") (pinfunction "NC_17") (pintype "passive+no_connect"))
    )
    (net (code "65") (name "unconnected-(U2-NC-Pad18)") (class "Default")
      (node (ref "U2") (pin "18") (pinfunction "NC_18") (pintype "passive+no_connect"))
    )
    (net (code "66") (name "unconnected-(U2-NC-Pad19)") (class "Default")
      (node (ref "U2") (pin "19") (pinfunction "NC_19") (pintype "passive+no_connect"))
    )
    (net (code "67") (name "unconnected-(U2-NC-Pad20)") (class "Default")
      (node (ref "U2") (pin "20") (pinfunction "NC_20") (pintype "passive+no_connect"))
    )
    (net (code "68") (name "unconnected-(U2-NC-Pad21)") (class "Default")
      (node (ref "U2") (pin "21") (pinfunction "NC_21") (pintype "passive+no_connect"))
    )
    (net (code "69") (name "unconnected-(U2-NC-Pad22)") (class "Default")
      (node (ref "U2") (pin "22") (pinfunction "NC_22") (pintype "passive+no_connect"))
    )
    (net (code "70") (name "unconnected-(U2-RI-Pad2)") (class "Default")
      (node (ref "U2") (pin "2") (pinfunction "RI_2") (pintype "input+no_connect"))
    )
    (net (code "71") (name "unconnected-(U2-RST-Pad9)") (class "Default")
      (node (ref "U2") (pin "9") (pinfunction "RST_9") (pintype "bidirectional+no_connect"))
    )
    (net (code "72") (name "unconnected-(U2-SUSPEND-Pad11)") (class "Default")
      (node (ref "U2") (pin "11") (pinfunction "SUSPEND_11") (pintype "output+no_connect"))
    )
    (net (code "73") (name "unconnected-(U2-SUSPEND-Pad12)") (class "Default")
      (node (ref "U2") (pin "12") (pinfunction "SUSPEND_12") (pintype "output+no_connect"))
    )
    (net (code "74") (name "unconnected-(U3-AD0-Pad7)") (class "Default")
      (node (ref "U3") (pin "7") (pinfunction "AD0_7") (pintype "input+no_connect"))
    )
    (net (code "75") (name "unconnected-(U3-INT-Pad8)") (class "Default")
      (node (ref "U3") (pin "8") (pinfunction "INT_8") (pintype "input+no_connect"))
    )
    (net (code "76") (name "unconnected-(U4-DRYD-Pad5)") (class "Default")
      (node (ref "U4") (pin "5") (pinfunction "DRYD_5") (pintype "output+no_connect"))
    )
    (net (code "77") (name "unconnected-(U5-CSB-Pad5)") (class "Default")
      (node (ref "U5") (pin "5") (pinfunction "CSB_5") (pintype "input+no_connect"))
    )
    (net (code "78") (name "unconnected-(U5-PS-Pad7)") (class "Default")
      (node (ref "U5") (pin "7") (pinfunction "PS_7") (pintype "input+no_connect"))
    )
    (net (code "79") (name "unconnected-(U5-SDO-Pad6)") (class "Default")
      (node (ref "U5") (pin "6") (pinfunction "SDO_6") (pintype "output+no_connect"))
    )
    (net (code "80") (name "unconnected-(USB1-ID-Pad4)") (class "Default")
      (node (ref "USB1") (pin "4") (pinfunction "ID_4") (pintype "bidirectional+no_connect"))
    )
    (net (code "81") (name "unconnected-(USB1-Pad0)") (class "Default")
      (node (ref "USB1") (pin "0") (pinfunction "0_0") (pintype "passive+no_connect"))
    )
  )
)
